# 01_-_Processor.net
KiCad netlist of a schematic drawn in Altium Designer
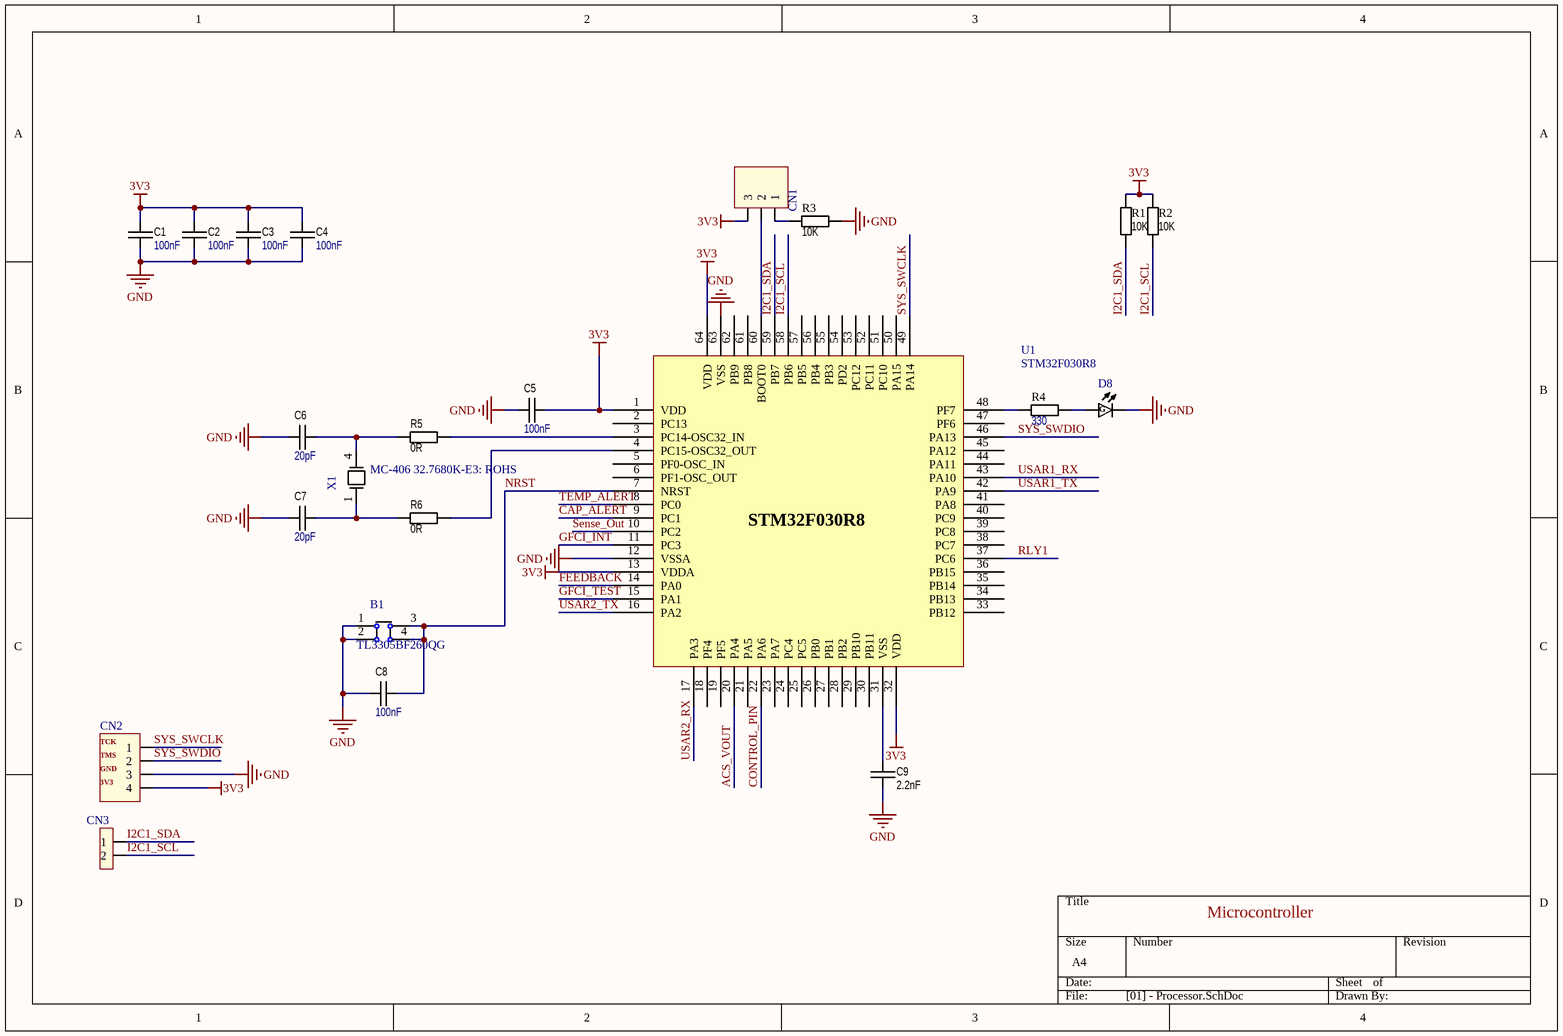
[diagram p0: [01] - Processor.SchDoc]

(export (version "E")
  (design (tool "Eeschema 10.0.6"))
  (components
    (comp (ref "B1")
      (value "TL3305BF260QG")
      (footprint "Switch")
      (description "Tactile Switch SPST-NO Top Actuated Surface Mount")
      (fields (field (name "MANUFACTURER") "E-Switch"))
      (libsource (lib "myLibrary") (part "SWITCH"))
    )
    (comp (ref "C1")
      (value "100nF")
      (footprint "CAP 0603/1608")
      (description "1µF ±10% 16V Ceramic Capacitor X5R 0603 (1608 Metric)")
      (fields (field (name "PARTNUMBER") "CC0603KRX5R7BB105") (field (name "MANUFACTURER") "Yageo"))
      (libsource (lib "myLibrary") (part "CAPC_100NF_0603_50V"))
    )
    (comp (ref "C2")
      (value "100nF")
      (footprint "CAP 0603/1608")
      (description "1µF ±10% 16V Ceramic Capacitor X5R 0603 (1608 Metric)")
      (fields (field (name "PARTNUMBER") "CC0603KRX5R7BB105") (field (name "MANUFACTURER") "Yageo"))
      (libsource (lib "myLibrary") (part "CAPC_100NF_0603_50V"))
    )
    (comp (ref "C3")
      (value "100nF")
      (footprint "CAP 0603/1608")
      (description "1µF ±10% 16V Ceramic Capacitor X5R 0603 (1608 Metric)")
      (fields (field (name "PARTNUMBER") "CC0603KRX5R7BB105") (field (name "MANUFACTURER") "Yageo"))
      (libsource (lib "myLibrary") (part "CAPC_100NF_0603_50V"))
    )
    (comp (ref "C4")
      (value "100nF")
      (footprint "CAP 0603/1608")
      (description "1µF ±10% 16V Ceramic Capacitor X5R 0603 (1608 Metric)")
      (fields (field (name "PARTNUMBER") "CC0603KRX5R7BB105") (field (name "MANUFACTURER") "Yageo"))
      (libsource (lib "myLibrary") (part "CAPC_100NF_0603_50V"))
    )
    (comp (ref "C5")
      (value "100nF")
      (footprint "CAP 0603/1608")
      (description "1µF ±10% 16V Ceramic Capacitor X5R 0603 (1608 Metric)")
      (fields (field (name "PARTNUMBER") "CC0603KRX5R7BB105") (field (name "MANUFACTURER") "Yageo"))
      (libsource (lib "myLibrary") (part "CAPC_100NF_0603_50V"))
    )
    (comp (ref "C6")
      (value "20pF")
      (footprint "CAP 0603/1608")
      (fields
        (field (name "PARTNUMBER") "CC0603JRNPO9BN200")
        (field (name "MANUFACTURER") "Yageo")
        (field (name "TOLERANCE") " ±5%")
      )
      (libsource (lib "myLibrary") (part "CAPC_20pF_0603_50V"))
    )
    (comp (ref "C7")
      (value "20pF")
      (footprint "CAP 0603/1608")
      (fields
        (field (name "PARTNUMBER") "CC0603JRNPO9BN200")
        (field (name "MANUFACTURER") "Yageo")
        (field (name "TOLERANCE") " ±5%")
      )
      (libsource (lib "myLibrary") (part "CAPC_20pF_0603_50V"))
    )
    (comp (ref "C8")
      (value "100nF")
      (footprint "CAP 0603/1608")
      (description "1µF ±10% 16V Ceramic Capacitor X5R 0603 (1608 Metric)")
      (fields (field (name "PARTNUMBER") "CC0603KRX5R7BB105") (field (name "MANUFACTURER") "Yageo"))
      (libsource (lib "myLibrary") (part "CAPC_100NF_0603_50V"))
    )
    (comp (ref "C9")
      (value "2.2nF")
      (footprint "CAP 0603/1608")
      (fields
        (field (name "PARTNUMBER") "C0603C222K5RACTU")
        (field (name "MANUFACTURER") "KEMET")
        (field (name "TOLERANCE") "±10%")
      )
      (libsource (lib "myLibrary") (part "CAPC_2.2uF_0603_50V"))
    )
    (comp (ref "CN1")
      (value "87220-3")
      (footprint "Terminal_3")
      (description "Connector Header Through Hole 3 position 0.100\" (2.54mm)")
      (fields (field (name "MANUFACTURER") "TE Connectivity AMP Connectors"))
      (libsource (lib "myLibrary") (part "CONN_3POS"))
    )
    (comp (ref "CN2")
      (value "61300411121")
      (footprint "Terminal_4")
      (description "Connector Header Through Hole 4 position 0.100\" (2.54mm)")
      (fields (field (name "MANUFACTURER") "Wurth Electronics Inc."))
      (libsource (lib "myLibrary") (part "CONN_4POS"))
    )
    (comp (ref "CN3")
      (value "5-146280-2")
      (footprint "Terminal_2")
      (description "Connector Header Through Hole 2 position 0.100\" (2.54mm)")
      (fields (field (name "MANUFACTURER") "TE Connectivity AMP Connectors"))
      (libsource (lib "myLibrary") (part "CONN_2POS"))
    )
    (comp (ref "D8")
      (value "SML-D12M8WT86")
      (footprint "LED-0603")
      (description "Green 572nm LED Indication - Discrete 2.2V 0603 (1608 Metric)")
      (fields (field (name "MANUFACTURER") "Rohm Semiconductor"))
      (libsource (lib "myLibrary") (part "LED_GREEN"))
    )
    (comp (ref "R1")
      (value "10K")
      (footprint "R0603")
      (fields (field (name "PARTNUMBER") "ESR03EZPF1002") (field (name "MANUFACTURER") "Rohm Semiconductor"))
      (libsource (lib "myLibrary") (part "RES_10K"))
    )
    (comp (ref "R2")
      (value "10K")
      (footprint "R0603")
      (fields (field (name "PARTNUMBER") "ESR03EZPF1002") (field (name "MANUFACTURER") "Rohm Semiconductor"))
      (libsource (lib "myLibrary") (part "RES_10K"))
    )
    (comp (ref "R3")
      (value "10K")
      (footprint "R0603")
      (fields (field (name "PARTNUMBER") "ESR03EZPF1002") (field (name "MANUFACTURER") "Rohm Semiconductor"))
      (libsource (lib "") (part "RES_10K_1"))
    )
    (comp (ref "R4")
      (value "330")
      (footprint "R0603")
      (description "330 Ohms ±1% 0.1W, 1/10W Chip Resistor 0603 (1608 Metric) Moisture Resistant Thick Film")
      (fields (field (name "PARTNUMBER") "RC0603FR-07330RL") (field (name "MANUFACTURER") "Yageo"))
      (libsource (lib "myLibrary") (part "RES_330_0603_1%"))
    )
    (comp (ref "R5")
      (value "0R")
      (footprint "R0603")
      (description "RES 0R 0603 JUMPER")
      (fields (field (name "PARTNUMBER") "RC0603JR-070RL") (field (name "MANUFACTURER") "Yageo"))
      (libsource (lib "myLibrary") (part "RES_0R_0603_JUMPER"))
    )
    (comp (ref "R6")
      (value "0R")
      (footprint "R0603")
      (description "RES 0R 0603 JUMPER")
      (fields (field (name "PARTNUMBER") "RC0603JR-070RL") (field (name "MANUFACTURER") "Yageo"))
      (libsource (lib "myLibrary") (part "RES_0R_0603_JUMPER"))
    )
    (comp (ref "U1")
      (value "STM32F030R8")
      (footprint "STM-LQFP64")
      (description "ARM® Cortex®-M0 STM32F0 Microcontroller IC 32-Bit 48MHz 64KB (64K x 8) FLASH 64-LQFP (10x10)")
      (fields
        (field (name "PARTNUMBER") "STM32F030R8T6TR")
        (field (name "MANUFACTURER") "STMicroelectronics")
      )
      (libsource (lib "myLibrary") (part "STM32F030R8"))
    )
    (comp (ref "X1")
      (value "MC-406 32.7680K-E3: ROHS")
      (footprint "XTAL_ABS25-32.768KHZ-6-T")
      (description "32.768kHz ±20ppm Crystal 6pF 35 kOhms 4-SOJ, 2.29mm pitch")
      (fields (field (name "MANUFACTURER") "EPSON"))
      (libsource (lib "myLibrary") (part "MC-406 32.7680K-E3{colon} ROHS"))
    )
  )
  (nets
    (net (code "1") (name "/ACS_VOUT") (class "Default")
      (node (ref "U1") (pin "20") (pinfunction "PA4_20") (pintype "passive"))
    )
    (net (code "2") (name "/CAP_ALERT") (class "Default")
      (node (ref "U1") (pin "9") (pinfunction "PC1_9") (pintype "passive"))
    )
    (net (code "3") (name "/CONTROL_PIN") (class "Default")
      (node (ref "U1") (pin "22") (pinfunction "PA6_22") (pintype "passive"))
    )
    (net (code "4") (name "/FEEDBACK") (class "Default")
      (node (ref "U1") (pin "14") (pinfunction "PA0_14") (pintype "passive"))
    )
    (net (code "5") (name "/GFCI_INT") (class "Default")
      (node (ref "U1") (pin "11") (pinfunction "PC3_11") (pintype "passive"))
    )
    (net (code "6") (name "/GFCI_TEST") (class "Default")
      (node (ref "U1") (pin "15") (pinfunction "PA1_15") (pintype "passive"))
    )
    (net (code "7") (name "/I2C1_SCL") (class "Default")
      (node (ref "CN3") (pin "2") (pinfunction "2_2") (pintype "passive"))
      (node (ref "R2") (pin "2") (pinfunction "2_2") (pintype "passive"))
      (node (ref "U1") (pin "58") (pinfunction "PB6_58") (pintype "passive"))
    )
    (net (code "8") (name "/I2C1_SDA") (class "Default")
      (node (ref "CN3") (pin "1") (pinfunction "1_1") (pintype "passive"))
      (node (ref "R1") (pin "2") (pinfunction "2_2") (pintype "passive"))
      (node (ref "U1") (pin "59") (pinfunction "PB7_59") (pintype "passive"))
    )
    (net (code "9") (name "/NRST") (class "Default")
      (node (ref "B1") (pin "3") (pinfunction "3_3") (pintype "passive"))
      (node (ref "B1") (pin "4") (pinfunction "4_4") (pintype "passive"))
      (node (ref "C8") (pin "2") (pintype "passive"))
      (node (ref "U1") (pin "7") (pinfunction "NRST_7") (pintype "passive"))
    )
    (net (code "10") (name "/RLY1") (class "Default")
      (node (ref "U1") (pin "37") (pinfunction "PC6_37") (pintype "passive"))
    )
    (net (code "11") (name "/SYS_SWCLK") (class "Default")
      (node (ref "CN2") (pin "1") (pinfunction "1_1") (pintype "passive"))
      (node (ref "U1") (pin "49") (pinfunction "PA14_49") (pintype "passive"))
    )
    (net (code "12") (name "/SYS_SWDIO") (class "Default")
      (node (ref "CN2") (pin "2") (pinfunction "2_2") (pintype "passive"))
      (node (ref "U1") (pin "46") (pinfunction "PA13_46") (pintype "passive"))
    )
    (net (code "13") (name "/Sense_Out") (class "Default")
      (node (ref "U1") (pin "10") (pinfunction "PC2_10") (pintype "passive"))
    )
    (net (code "14") (name "/TEMP_ALERT") (class "Default")
      (node (ref "U1") (pin "8") (pinfunction "PC0_8") (pintype "passive"))
    )
    (net (code "15") (name "/USAR1_RX") (class "Default")
      (node (ref "U1") (pin "43") (pinfunction "PA10_43") (pintype "passive"))
    )
    (net (code "16") (name "/USAR1_TX") (class "Default")
      (node (ref "U1") (pin "42") (pinfunction "PA9_42") (pintype "passive"))
    )
    (net (code "17") (name "/USAR2_RX") (class "Default")
      (node (ref "U1") (pin "17") (pinfunction "PA3_17") (pintype "passive"))
    )
    (net (code "18") (name "/USAR2_TX") (class "Default")
      (node (ref "U1") (pin "16") (pinfunction "PA2_16") (pintype "passive"))
    )
    (net (code "19") (name "3V3") (class "Default")
      (node (ref "C1") (pin "1") (pintype "passive"))
      (node (ref "C2") (pin "1") (pintype "passive"))
      (node (ref "C3") (pin "1") (pintype "passive"))
      (node (ref "C4") (pin "1") (pintype "passive"))
      (node (ref "C5") (pin "2") (pintype "passive"))
      (node (ref "CN1") (pin "3") (pinfunction "3_3") (pintype "passive"))
      (node (ref "CN2") (pin "4") (pinfunction "4_4") (pintype "passive"))
      (node (ref "R1") (pin "1") (pinfunction "1_1") (pintype "passive"))
      (node (ref "R2") (pin "1") (pinfunction "1_1") (pintype "passive"))
      (node (ref "U1") (pin "1") (pinfunction "VDD_1") (pintype "passive"))
      (node (ref "U1") (pin "13") (pinfunction "VDDA_13") (pintype "passive"))
      (node (ref "U1") (pin "32") (pinfunction "VDD_32") (pintype "passive"))
      (node (ref "U1") (pin "64") (pinfunction "VDD_64") (pintype "passive"))
    )
    (net (code "20") (name "GND") (class "Default")
      (node (ref "B1") (pin "1") (pinfunction "1_1") (pintype "passive"))
      (node (ref "B1") (pin "2") (pinfunction "2_2") (pintype "passive"))
      (node (ref "C1") (pin "2") (pintype "passive"))
      (node (ref "C2") (pin "2") (pintype "passive"))
      (node (ref "C3") (pin "2") (pintype "passive"))
      (node (ref "C4") (pin "2") (pintype "passive"))
      (node (ref "C5") (pin "1") (pintype "passive"))
      (node (ref "C6") (pin "1") (pintype "passive"))
      (node (ref "C7") (pin "1") (pintype "passive"))
      (node (ref "C8") (pin "1") (pintype "passive"))
      (node (ref "C9") (pin "2") (pintype "passive"))
      (node (ref "CN2") (pin "3") (pinfunction "3_3") (pintype "passive"))
      (node (ref "D8") (pin "1") (pinfunction "1_1") (pintype "passive"))
      (node (ref "R3") (pin "1") (pinfunction "1_1") (pintype "passive"))
      (node (ref "U1") (pin "12") (pinfunction "VSSA_12") (pintype "passive"))
      (node (ref "U1") (pin "63") (pinfunction "VSS_63") (pintype "passive"))
    )
    (net (code "21") (name "Net-(C6-Pad2)") (class "Default")
      (node (ref "C6") (pin "2") (pintype "passive"))
      (node (ref "R5") (pin "1") (pinfunction "1_1") (pintype "passive"))
      (node (ref "X1") (pin "4") (pinfunction "4_4") (pintype "passive"))
    )
    (net (code "22") (name "Net-(C7-Pad2)") (class "Default")
      (node (ref "C7") (pin "2") (pintype "passive"))
      (node (ref "R6") (pin "1") (pinfunction "1_1") (pintype "passive"))
      (node (ref "X1") (pin "1") (pinfunction "1_1") (pintype "passive"))
    )
    (net (code "23") (name "Net-(C9-Pad1)") (class "Default")
      (node (ref "C9") (pin "1") (pintype "passive"))
      (node (ref "U1") (pin "31") (pinfunction "VSS_31") (pintype "passive"))
    )
    (net (code "24") (name "Net-(CN1-Pad1)") (class "Default")
      (node (ref "CN1") (pin "1") (pinfunction "1_1") (pintype "passive"))
      (node (ref "R3") (pin "2") (pinfunction "2_2") (pintype "passive"))
    )
    (net (code "25") (name "Net-(D8-Pad2)") (class "Default")
      (node (ref "D8") (pin "2") (pinfunction "2_2") (pintype "passive"))
      (node (ref "R4") (pin "2") (pinfunction "2_2") (pintype "passive"))
    )
    (net (code "26") (name "Net-(U1-BOOT0)") (class "Default")
      (node (ref "CN1") (pin "2") (pinfunction "2_2") (pintype "passive"))
      (node (ref "U1") (pin "60") (pinfunction "BOOT0_60") (pintype "passive"))
    )
    (net (code "27") (name "Net-(U1-PC14-OSC32_IN)") (class "Default")
      (node (ref "R5") (pin "2") (pinfunction "2_2") (pintype "passive"))
      (node (ref "U1") (pin "3") (pinfunction "PC14-OSC32_IN_3") (pintype "passive"))
    )
    (net (code "28") (name "Net-(U1-PC15-OSC32_OUT)") (class "Default")
      (node (ref "R6") (pin "2") (pinfunction "2_2") (pintype "passive"))
      (node (ref "U1") (pin "4") (pinfunction "PC15-OSC32_OUT_4") (pintype "passive"))
    )
    (net (code "29") (name "Net-(U1-PF7)") (class "Default")
      (node (ref "R4") (pin "1") (pinfunction "1_1") (pintype "passive"))
      (node (ref "U1") (pin "48") (pinfunction "PF7_48") (pintype "passive"))
    )
    (net (code "30") (name "unconnected-(U1-PA5-Pad21)") (class "Default")
      (node (ref "U1") (pin "21") (pinfunction "PA5_21") (pintype "passive"))
    )
    (net (code "31") (name "unconnected-(U1-PA7-Pad23)") (class "Default")
      (node (ref "U1") (pin "23") (pinfunction "PA7_23") (pintype "passive"))
    )
    (net (code "32") (name "unconnected-(U1-PA8-Pad41)") (class "Default")
      (node (ref "U1") (pin "41") (pinfunction "PA8_41") (pintype "passive"))
    )
    (net (code "33") (name "unconnected-(U1-PA11-Pad44)") (class "Default")
      (node (ref "U1") (pin "44") (pinfunction "PA11_44") (pintype "passive"))
    )
    (net (code "34") (name "unconnected-(U1-PA12-Pad45)") (class "Default")
      (node (ref "U1") (pin "45") (pinfunction "PA12_45") (pintype "passive"))
    )
    (net (code "35") (name "unconnected-(U1-PA15-Pad50)") (class "Default")
      (node (ref "U1") (pin "50") (pinfunction "PA15_50") (pintype "passive"))
    )
    (net (code "36") (name "unconnected-(U1-PB0-Pad26)") (class "Default")
      (node (ref "U1") (pin "26") (pinfunction "PB0_26") (pintype "passive"))
    )
    (net (code "37") (name "unconnected-(U1-PB1-Pad27)") (class "Default")
      (node (ref "U1") (pin "27") (pinfunction "PB1_27") (pintype "passive"))
    )
    (net (code "38") (name "unconnected-(U1-PB2-Pad28)") (class "Default")
      (node (ref "U1") (pin "28") (pinfunction "PB2_28") (pintype "passive"))
    )
    (net (code "39") (name "unconnected-(U1-PB3-Pad55)") (class "Default")
      (node (ref "U1") (pin "55") (pinfunction "PB3_55") (pintype "passive"))
    )
    (net (code "40") (name "unconnected-(U1-PB4-Pad56)") (class "Default")
      (node (ref "U1") (pin "56") (pinfunction "PB4_56") (pintype "passive"))
    )
    (net (code "41") (name "unconnected-(U1-PB5-Pad57)") (class "Default")
      (node (ref "U1") (pin "57") (pinfunction "PB5_57") (pintype "passive"))
    )
    (net (code "42") (name "unconnected-(U1-PB8-Pad61)") (class "Default")
      (node (ref "U1") (pin "61") (pinfunction "PB8_61") (pintype "passive"))
    )
    (net (code "43") (name "unconnected-(U1-PB9-Pad62)") (class "Default")
      (node (ref "U1") (pin "62") (pinfunction "PB9_62") (pintype "passive"))
    )
    (net (code "44") (name "unconnected-(U1-PB10-Pad29)") (class "Default")
      (node (ref "U1") (pin "29") (pinfunction "PB10_29") (pintype "passive"))
    )
    (net (code "45") (name "unconnected-(U1-PB11-Pad30)") (class "Default")
      (node (ref "U1") (pin "30") (pinfunction "PB11_30") (pintype "passive"))
    )
    (net (code "46") (name "unconnected-(U1-PB12-Pad33)") (class "Default")
      (node (ref "U1") (pin "33") (pinfunction "PB12_33") (pintype "passive"))
    )
    (net (code "47") (name "unconnected-(U1-PB13-Pad34)") (class "Default")
      (node (ref "U1") (pin "34") (pinfunction "PB13_34") (pintype "passive"))
    )
    (net (code "48") (name "unconnected-(U1-PB14-Pad35)") (class "Default")
      (node (ref "U1") (pin "35") (pinfunction "PB14_35") (pintype "passive"))
    )
    (net (code "49") (name "unconnected-(U1-PB15-Pad36)") (class "Default")
      (node (ref "U1") (pin "36") (pinfunction "PB15_36") (pintype "passive"))
    )
    (net (code "50") (name "unconnected-(U1-PC4-Pad24)") (class "Default")
      (node (ref "U1") (pin "24") (pinfunction "PC4_24") (pintype "passive"))
    )
    (net (code "51") (name "unconnected-(U1-PC5-Pad25)") (class "Default")
      (node (ref "U1") (pin "25") (pinfunction "PC5_25") (pintype "passive"))
    )
    (net (code "52") (name "unconnected-(U1-PC7-Pad38)") (class "Default")
      (node (ref "U1") (pin "38") (pinfunction "PC7_38") (pintype "passive"))
    )
    (net (code "53") (name "unconnected-(U1-PC8-Pad39)") (class "Default")
      (node (ref "U1") (pin "39") (pinfunction "PC8_39") (pintype "passive"))
    )
    (net (code "54") (name "unconnected-(U1-PC9-Pad40)") (class "Default")
      (node (ref "U1") (pin "40") (pinfunction "PC9_40") (pintype "passive"))
    )
    (net (code "55") (name "unconnected-(U1-PC10-Pad51)") (class "Default")
      (node (ref "U1") (pin "51") (pinfunction "PC10_51") (pintype "passive"))
    )
    (net (code "56") (name "unconnected-(U1-PC11-Pad52)") (class "Default")
      (node (ref "U1") (pin "52") (pinfunction "PC11_52") (pintype "passive"))
    )
    (net (code "57") (name "unconnected-(U1-PC12-Pad53)") (class "Default")
      (node (ref "U1") (pin "53") (pinfunction "PC12_53") (pintype "passive"))
    )
    (net (code "58") (name "unconnected-(U1-PC13-Pad2)") (class "Default")
      (node (ref "U1") (pin "2") (pinfunction "PC13_2") (pintype "passive"))
    )
    (net (code "59") (name "unconnected-(U1-PD2-Pad54)") (class "Default")
      (node (ref "U1") (pin "54") (pinfunction "PD2_54") (pintype "passive"))
    )
    (net (code "60") (name "unconnected-(U1-PF0-OSC_IN-Pad5)") (class "Default")
      (node (ref "U1") (pin "5") (pinfunction "PF0-OSC_IN_5") (pintype "passive"))
    )
    (net (code "61") (name "unconnected-(U1-PF1-OSC_OUT-Pad6)") (class "Default")
      (node (ref "U1") (pin "6") (pinfunction "PF1-OSC_OUT_6") (pintype "passive"))
    )
    (net (code "62") (name "unconnected-(U1-PF4-Pad18)") (class "Default")
      (node (ref "U1") (pin "18") (pinfunction "PF4_18") (pintype "passive"))
    )
    (net (code "63") (name "unconnected-(U1-PF5-Pad19)") (class "Default")
      (node (ref "U1") (pin "19") (pinfunction "PF5_19") (pintype "passive"))
    )
    (net (code "64") (name "unconnected-(U1-PF6-Pad47)") (class "Default")
      (node (ref "U1") (pin "47") (pinfunction "PF6_47") (pintype "passive"))
    )
  )
)
